# M5stamp_round_lcd.net
KiCad netlist of a schematic drawn in EAGLE
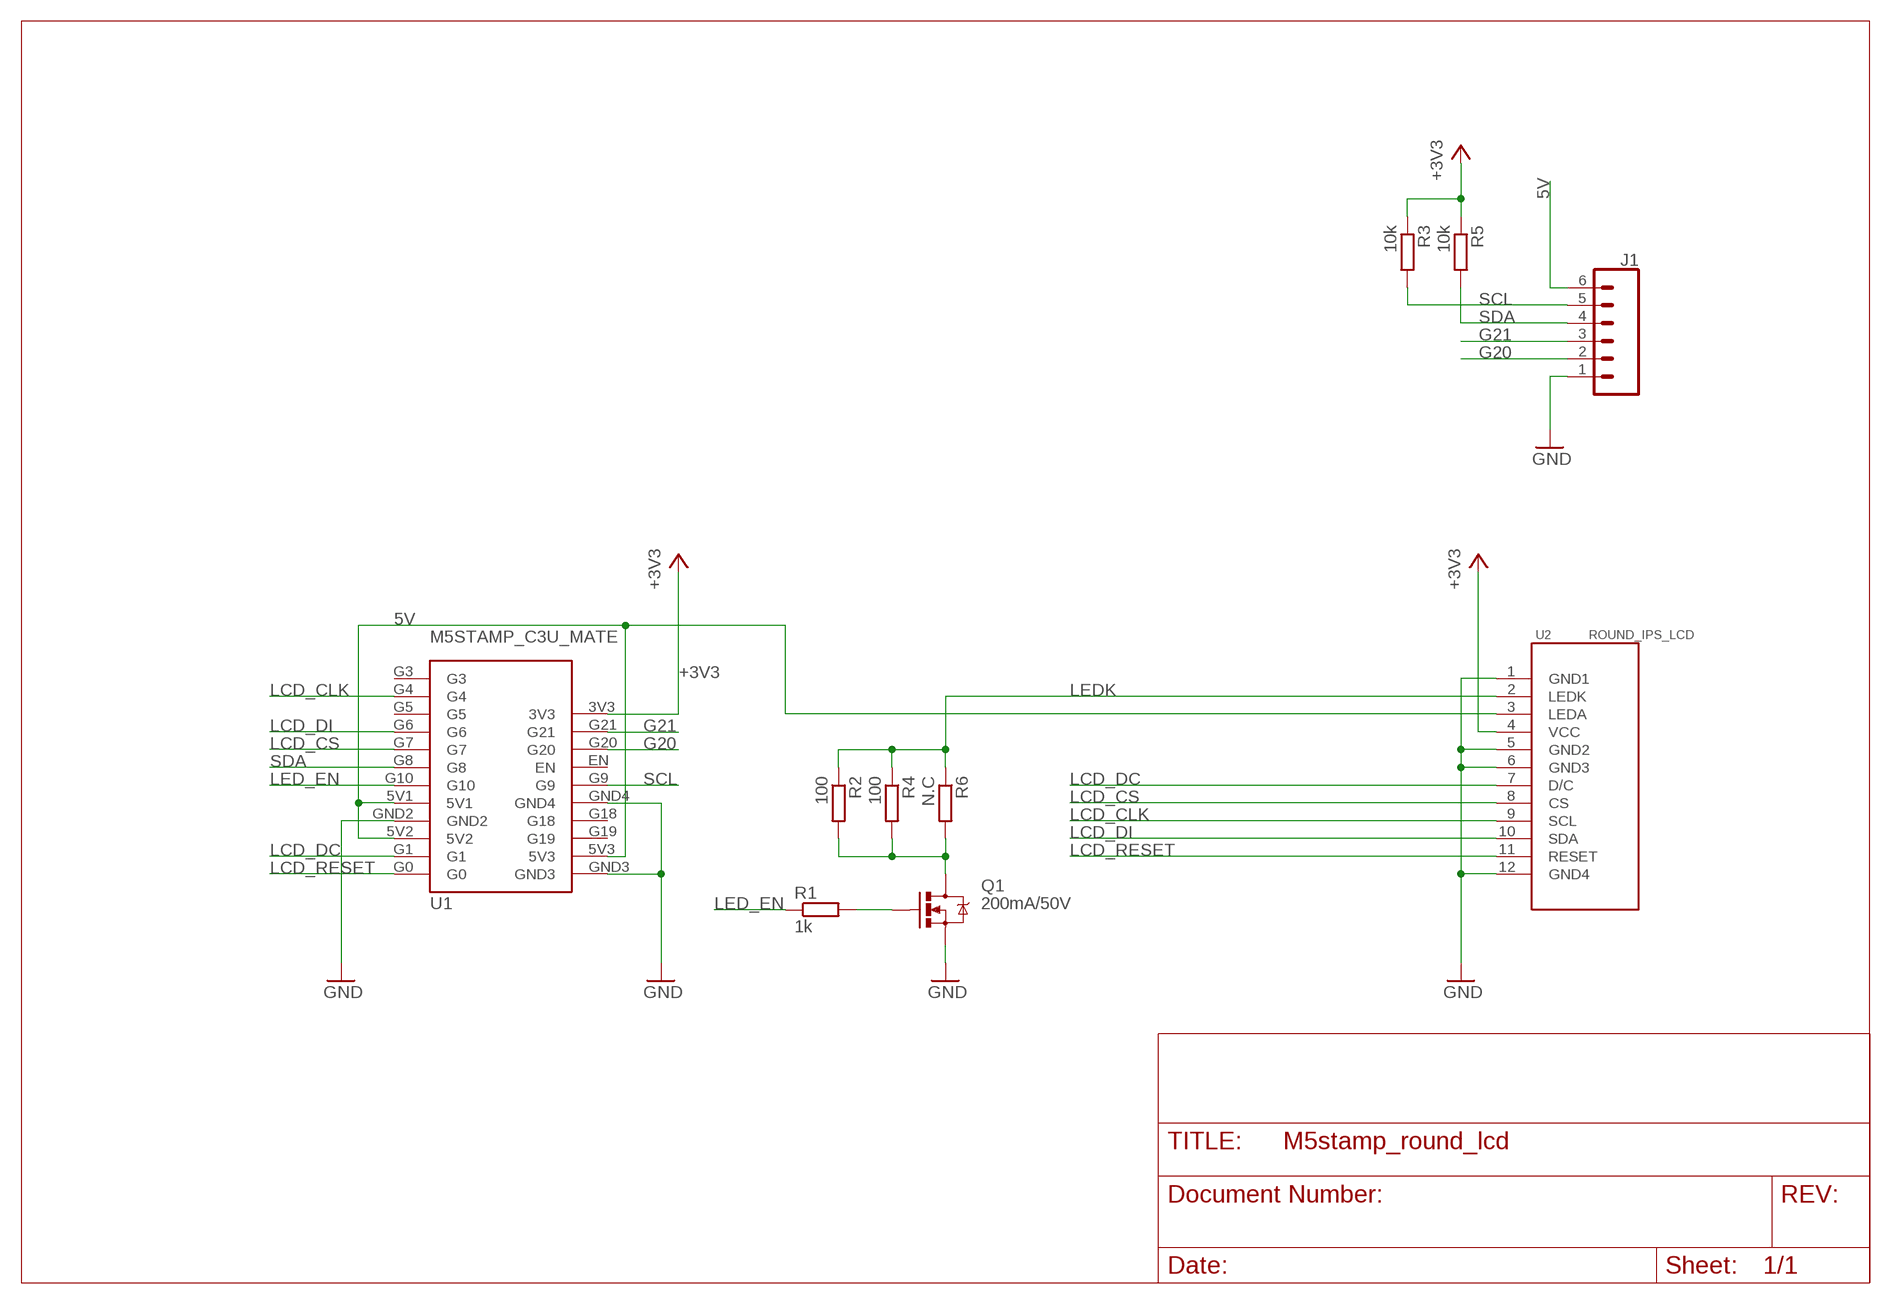
[diagram p0: schematic, sheet 1]

(export (version "E")
  (design (tool "Eeschema 10.0.6"))
  (components
    (comp (ref "J1")
      (value "CONN_06SILK_FEMALE_PTH")
      (footprint "eagle-import:1X06")
      (libsource (lib "eagle-import") (part "CONN_06SILK_FEMALE_PTH"))
    )
    (comp (ref "Q1")
      (value "200mA/50V")
      (footprint "eagle-import:SOT23-3")
      (libsource (lib "eagle-import") (part "MOSFET-NCHANNELBSS138"))
    )
    (comp (ref "R1")
      (value "1k")
      (footprint "eagle-import:R0603")
      (libsource (lib "eagle-import") (part "R-EU_R0603"))
    )
    (comp (ref "R2")
      (value "100")
      (footprint "eagle-import:R0603")
      (libsource (lib "eagle-import") (part "R-EU_R0603"))
    )
    (comp (ref "R3")
      (value "10k")
      (footprint "eagle-import:R0603")
      (libsource (lib "eagle-import") (part "R-EU_R0603"))
    )
    (comp (ref "R4")
      (value "100")
      (footprint "eagle-import:R0603")
      (libsource (lib "eagle-import") (part "R-EU_R0603"))
    )
    (comp (ref "R5")
      (value "10k")
      (footprint "eagle-import:R0603")
      (libsource (lib "eagle-import") (part "R-EU_R0603"))
    )
    (comp (ref "R6")
      (value "N.C")
      (footprint "eagle-import:R0603")
      (libsource (lib "eagle-import") (part "R-EU_R0603"))
    )
    (comp (ref "U1")
      (value "M5STAMP_C3U_MATE")
      (footprint "eagle-import:M5STAMPC3UMATE")
      (libsource (lib "eagle-import") (part "M5STAMP_C3U_MATE"))
    )
    (comp (ref "U2")
      (value "ROUND_IPS_LCD")
      (footprint "eagle-import:ROUND_IPS_LCD")
      (libsource (lib "eagle-import") (part "ROUND_IPS_LCD"))
    )
  )
  (nets
    (net (code "1") (name "+3V3") (class "Default")
      (node (ref "R3") (pin "1") (pinfunction "1_1") (pintype "passive"))
      (node (ref "R5") (pin "1") (pinfunction "1_1") (pintype "passive"))
      (node (ref "U1") (pin "3V3") (pinfunction "3V3_3V3") (pintype "bidirectional"))
      (node (ref "U2") (pin "4") (pinfunction "VCC_4") (pintype "power_in"))
    )
    (net (code "2") (name "/5V") (class "Default")
      (node (ref "J1") (pin "6") (pinfunction "6_6") (pintype "passive"))
      (node (ref "U1") (pin "5V1") (pinfunction "5V1_5V1") (pintype "bidirectional"))
      (node (ref "U1") (pin "5V2") (pinfunction "5V2_5V2") (pintype "bidirectional"))
      (node (ref "U1") (pin "5V3") (pinfunction "5V3_5V3") (pintype "bidirectional"))
      (node (ref "U2") (pin "3") (pinfunction "LEDA_3") (pintype "bidirectional"))
    )
    (net (code "3") (name "/G20") (class "Default")
      (node (ref "J1") (pin "2") (pinfunction "2_2") (pintype "passive"))
      (node (ref "U1") (pin "G20") (pinfunction "G20_G20") (pintype "bidirectional"))
    )
    (net (code "4") (name "/G21") (class "Default")
      (node (ref "J1") (pin "3") (pinfunction "3_3") (pintype "passive"))
      (node (ref "U1") (pin "G21") (pinfunction "G21_G21") (pintype "bidirectional"))
    )
    (net (code "5") (name "/LCD_CLK") (class "Default")
      (node (ref "U1") (pin "G4") (pinfunction "G4_G4") (pintype "bidirectional"))
      (node (ref "U2") (pin "9") (pinfunction "SCL_9") (pintype "input"))
    )
    (net (code "6") (name "/LCD_CS") (class "Default")
      (node (ref "U1") (pin "G7") (pinfunction "G7_G7") (pintype "bidirectional"))
      (node (ref "U2") (pin "8") (pinfunction "CS_8") (pintype "input"))
    )
    (net (code "7") (name "/LCD_DC") (class "Default")
      (node (ref "U1") (pin "G1") (pinfunction "G1_G1") (pintype "bidirectional"))
      (node (ref "U2") (pin "7") (pinfunction "D/C_7") (pintype "input"))
    )
    (net (code "8") (name "/LCD_DI") (class "Default")
      (node (ref "U1") (pin "G6") (pinfunction "G6_G6") (pintype "bidirectional"))
      (node (ref "U2") (pin "10") (pinfunction "SDA_10") (pintype "bidirectional"))
    )
    (net (code "9") (name "/LCD_RESET") (class "Default")
      (node (ref "U1") (pin "G0") (pinfunction "G0_G0") (pintype "bidirectional"))
      (node (ref "U2") (pin "11") (pinfunction "RESET_11") (pintype "input"))
    )
    (net (code "10") (name "/LEDK") (class "Default")
      (node (ref "R2") (pin "1") (pinfunction "1_1") (pintype "passive"))
      (node (ref "R4") (pin "1") (pinfunction "1_1") (pintype "passive"))
      (node (ref "R6") (pin "1") (pinfunction "1_1") (pintype "passive"))
      (node (ref "U2") (pin "2") (pinfunction "LEDK_2") (pintype "bidirectional"))
    )
    (net (code "11") (name "/LED_EN") (class "Default")
      (node (ref "R1") (pin "1") (pinfunction "1_1") (pintype "passive"))
      (node (ref "U1") (pin "G10") (pinfunction "G10_G10") (pintype "bidirectional"))
    )
    (net (code "12") (name "/SCL") (class "Default")
      (node (ref "J1") (pin "5") (pinfunction "5_5") (pintype "passive"))
      (node (ref "R3") (pin "2") (pinfunction "2_2") (pintype "passive"))
      (node (ref "U1") (pin "G9") (pinfunction "G9_G9") (pintype "bidirectional"))
    )
    (net (code "13") (name "/SDA") (class "Default")
      (node (ref "J1") (pin "4") (pinfunction "4_4") (pintype "passive"))
      (node (ref "R5") (pin "2") (pinfunction "2_2") (pintype "passive"))
      (node (ref "U1") (pin "G8") (pinfunction "G8_G8") (pintype "bidirectional"))
    )
    (net (code "14") (name "GND") (class "Default")
      (node (ref "J1") (pin "1") (pinfunction "1_1") (pintype "passive"))
      (node (ref "Q1") (pin "2") (pinfunction "S_2") (pintype "passive"))
      (node (ref "U1") (pin "GND2") (pinfunction "GND2_GND2") (pintype "bidirectional"))
      (node (ref "U1") (pin "GND3") (pinfunction "GND3_GND3") (pintype "bidirectional"))
      (node (ref "U1") (pin "GND4") (pinfunction "GND4_GND4") (pintype "bidirectional"))
      (node (ref "U2") (pin "1") (pinfunction "GND1_1") (pintype "power_in"))
      (node (ref "U2") (pin "12") (pinfunction "GND4_12") (pintype "power_in"))
      (node (ref "U2") (pin "5") (pinfunction "GND2_5") (pintype "power_in"))
      (node (ref "U2") (pin "6") (pinfunction "GND3_6") (pintype "power_in"))
    )
    (net (code "15") (name "Net-(Q1-D)") (class "Default")
      (node (ref "Q1") (pin "3") (pinfunction "D_3") (pintype "passive"))
      (node (ref "R2") (pin "2") (pinfunction "2_2") (pintype "passive"))
      (node (ref "R4") (pin "2") (pinfunction "2_2") (pintype "passive"))
      (node (ref "R6") (pin "2") (pinfunction "2_2") (pintype "passive"))
    )
    (net (code "16") (name "Net-(Q1-G)") (class "Default")
      (node (ref "Q1") (pin "1") (pinfunction "G_1") (pintype "passive"))
      (node (ref "R1") (pin "2") (pinfunction "2_2") (pintype "passive"))
    )
    (net (code "17") (name "unconnected-(U1-PadEN)") (class "Default")
      (node (ref "U1") (pin "EN") (pinfunction "EN_EN") (pintype "bidirectional"))
    )
    (net (code "18") (name "unconnected-(U1-PadG3)") (class "Default")
      (node (ref "U1") (pin "G3") (pinfunction "G3_G3") (pintype "bidirectional"))
    )
    (net (code "19") (name "unconnected-(U1-PadG5)") (class "Default")
      (node (ref "U1") (pin "G5") (pinfunction "G5_G5") (pintype "bidirectional"))
    )
    (net (code "20") (name "unconnected-(U1-PadG18)") (class "Default")
      (node (ref "U1") (pin "G18") (pinfunction "G18_G18") (pintype "bidirectional"))
    )
    (net (code "21") (name "unconnected-(U1-PadG19)") (class "Default")
      (node (ref "U1") (pin "G19") (pinfunction "G19_G19") (pintype "bidirectional"))
    )
  )
)
